# untitled.net
KiCad netlist of a schematic drawn in EAGLE
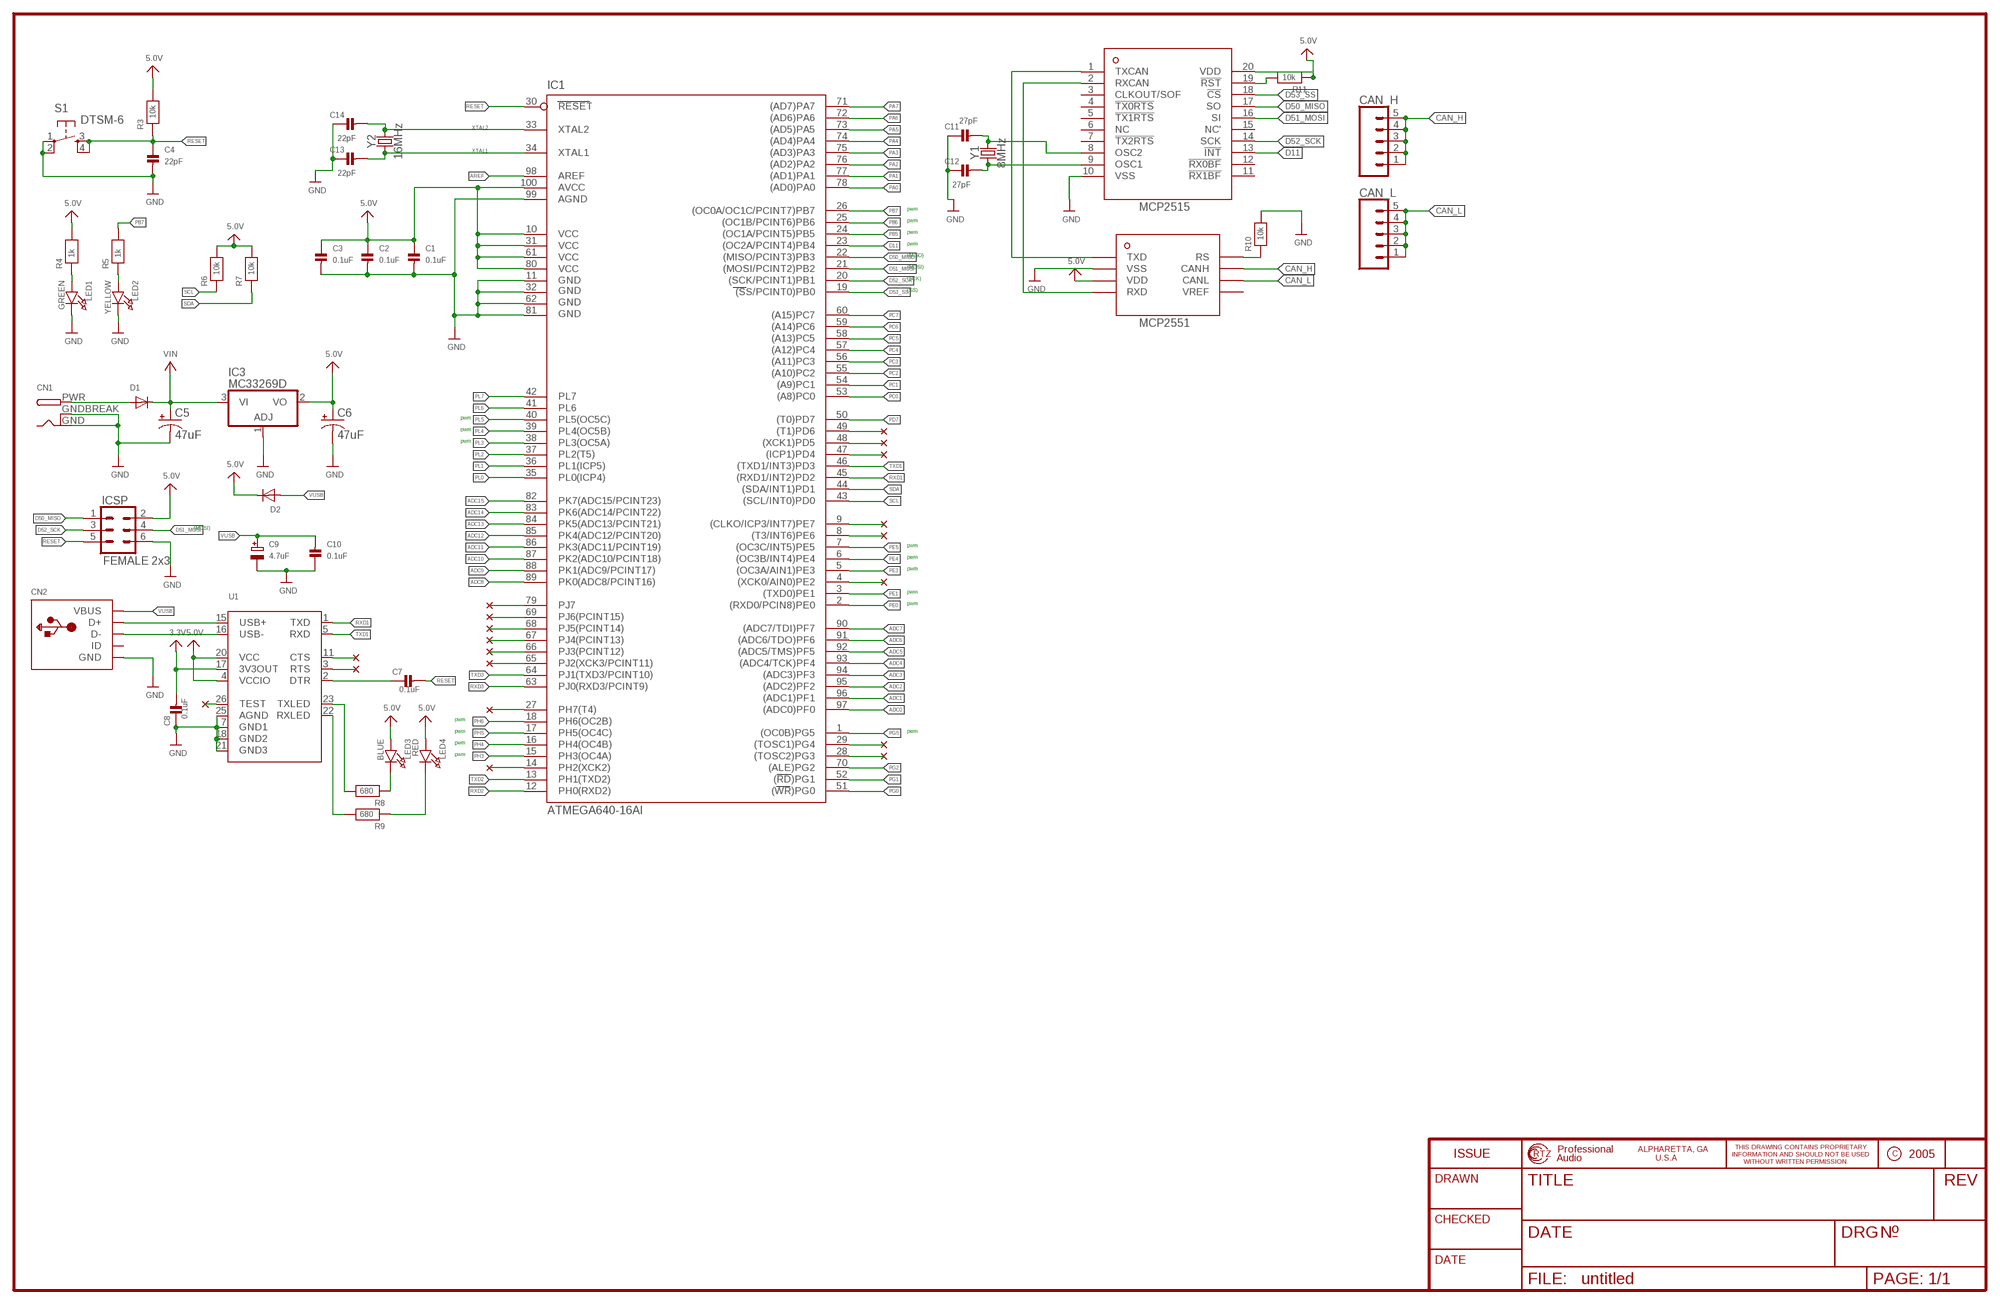
[diagram p0: schematic, sheet 1]

(export (version "E")
  (design (tool "Eeschema 10.0.6"))
  (components
    (comp (ref "C1")
      (value "0.1uF")
      (footprint "eagle-import:0805")
      (libsource (lib "eagle-import") (part "CAP_CERAMIC0805"))
    )
    (comp (ref "C2")
      (value "0.1uF")
      (footprint "eagle-import:0805")
      (libsource (lib "eagle-import") (part "CAP_CERAMIC0805"))
    )
    (comp (ref "C3")
      (value "0.1uF")
      (footprint "eagle-import:0805")
      (libsource (lib "eagle-import") (part "CAP_CERAMIC0805"))
    )
    (comp (ref "C4")
      (value "22pF")
      (footprint "eagle-import:0805")
      (libsource (lib "eagle-import") (part "CAP_CERAMIC0805"))
    )
    (comp (ref "C5")
      (value "47uF")
      (footprint "eagle-import:PANASONIC_D")
      (libsource (lib "eagle-import") (part "CPOL-USD"))
    )
    (comp (ref "C6")
      (value "47uF")
      (footprint "eagle-import:PANASONIC_D")
      (libsource (lib "eagle-import") (part "CPOL-USD"))
    )
    (comp (ref "C7")
      (value "0.1uF")
      (footprint "eagle-import:0805")
      (libsource (lib "eagle-import") (part "CAP_CERAMIC0805"))
    )
    (comp (ref "C8")
      (value "0.1uF")
      (footprint "eagle-import:0805")
      (libsource (lib "eagle-import") (part "CAP_CERAMIC0805"))
    )
    (comp (ref "C9")
      (value "4.7uF")
      (footprint "eagle-import:EIA7343-31_D-W")
      (libsource (lib "eagle-import") (part "CAP_TANTALUMD/7343_WAVE"))
    )
    (comp (ref "C10")
      (value "0.1uF")
      (footprint "eagle-import:0805")
      (libsource (lib "eagle-import") (part "CAP_CERAMIC0805"))
    )
    (comp (ref "C11")
      (value "27pF")
      (footprint "eagle-import:0805")
      (libsource (lib "eagle-import") (part "CAP_CERAMIC0805"))
    )
    (comp (ref "C12")
      (value "27pF")
      (footprint "eagle-import:0805")
      (libsource (lib "eagle-import") (part "CAP_CERAMIC0805"))
    )
    (comp (ref "C13")
      (value "22pF")
      (footprint "eagle-import:0805")
      (libsource (lib "eagle-import") (part "CAP_CERAMIC0805"))
    )
    (comp (ref "C14")
      (value "22pF")
      (footprint "eagle-import:0805")
      (libsource (lib "eagle-import") (part "CAP_CERAMIC0805"))
    )
    (comp (ref "CAN_H")
      (value "CONN_05SCREW")
      (footprint "eagle-import:SCREWTERMINAL-3.5MM-5")
      (libsource (lib "eagle-import") (part "CONN_05SCREW"))
    )
    (comp (ref "CAN_L")
      (value "CONN_05SCREW")
      (footprint "eagle-import:SCREWTERMINAL-3.5MM-5")
      (libsource (lib "eagle-import") (part "CONN_05SCREW"))
    )
    (comp (ref "CN1")
      (value "DCBARRELPTH")
      (footprint "eagle-import:DCJACK_2MM_PTH")
      (libsource (lib "eagle-import") (part "DCBARRELPTH"))
    )
    (comp (ref "CN2")
      (value "USBMINIB")
      (footprint "eagle-import:USB-MINIB")
      (libsource (lib "eagle-import") (part "USBMINIB"))
    )
    (comp (ref "D1")
      (value "DIODESOD-123")
      (footprint "eagle-import:SOD-123")
      (libsource (lib "eagle-import") (part "DIODESOD-123"))
    )
    (comp (ref "D2")
      (value "DIODESOD-123")
      (footprint "eagle-import:SOD-123")
      (libsource (lib "eagle-import") (part "DIODESOD-123"))
    )
    (comp (ref "IC1")
      (value "ATMEGA640-16AI")
      (footprint "eagle-import:TQFP100")
      (libsource (lib "eagle-import") (part "ATMEGAAI640-16"))
    )
    (comp (ref "IC3")
      (value "MC33269D")
      (footprint "eagle-import:DPACK")
      (libsource (lib "eagle-import") (part "MC33269?D"))
    )
    (comp (ref "ICSP")
      (value "FEMALE 2x3")
      (footprint "eagle-import:2X3")
      (libsource (lib "eagle-import") (part "CONN_03X2FEMALE"))
    )
    (comp (ref "LED1")
      (value "GREEN")
      (footprint "eagle-import:CHIPLED_0805")
      (libsource (lib "eagle-import") (part "LED0805"))
    )
    (comp (ref "LED2")
      (value "YELLOW")
      (footprint "eagle-import:CHIPLED_0805")
      (libsource (lib "eagle-import") (part "LED0805"))
    )
    (comp (ref "LED3")
      (value "BLUE")
      (footprint "eagle-import:CHIPLED_0805")
      (libsource (lib "eagle-import") (part "LED0805"))
    )
    (comp (ref "LED4")
      (value "RED")
      (footprint "eagle-import:CHIPLED_0805")
      (libsource (lib "eagle-import") (part "LED0805"))
    )
    (comp (ref "R3")
      (value "10k")
      (footprint "eagle-import:0805")
      (libsource (lib "eagle-import") (part "RESISTOR0805"))
    )
    (comp (ref "R4")
      (value "1k")
      (footprint "eagle-import:0805")
      (libsource (lib "eagle-import") (part "RESISTOR0805"))
    )
    (comp (ref "R5")
      (value "1k")
      (footprint "eagle-import:0805")
      (libsource (lib "eagle-import") (part "RESISTOR0805"))
    )
    (comp (ref "R6")
      (value "10k")
      (footprint "eagle-import:0805")
      (libsource (lib "eagle-import") (part "RESISTOR0805"))
    )
    (comp (ref "R7")
      (value "10k")
      (footprint "eagle-import:0805")
      (libsource (lib "eagle-import") (part "RESISTOR0805"))
    )
    (comp (ref "R8")
      (value "680")
      (footprint "eagle-import:0805")
      (libsource (lib "eagle-import") (part "RESISTOR0805"))
    )
    (comp (ref "R9")
      (value "680")
      (footprint "eagle-import:0805")
      (libsource (lib "eagle-import") (part "RESISTOR0805"))
    )
    (comp (ref "R10")
      (value "10k")
      (footprint "eagle-import:0805")
      (libsource (lib "eagle-import") (part "RESISTOR0805"))
    )
    (comp (ref "R11")
      (value "10k")
      (footprint "eagle-import:0805")
      (libsource (lib "eagle-import") (part "RESISTOR0805"))
    )
    (comp (ref "S1")
      (value "DTSM-6")
      (footprint "eagle-import:DTSM-6")
      (libsource (lib "eagle-import") (part "DTSM-6"))
    )
    (comp (ref "U$6") (value "NC") (footprint "eagle-import:NC") (libsource (lib "eagle-import") (part "NC")))
    (comp (ref "U$7") (value "NC") (footprint "eagle-import:NC") (libsource (lib "eagle-import") (part "NC")))
    (comp (ref "U$8") (value "NC") (footprint "eagle-import:NC") (libsource (lib "eagle-import") (part "NC")))
    (comp (ref "U$9") (value "NC") (footprint "eagle-import:NC") (libsource (lib "eagle-import") (part "NC")))
    (comp (ref "U$10")
      (value "NC")
      (footprint "eagle-import:NC")
      (libsource (lib "eagle-import") (part "NC"))
    )
    (comp (ref "U$11")
      (value "NC")
      (footprint "eagle-import:NC")
      (libsource (lib "eagle-import") (part "NC"))
    )
    (comp (ref "U$12")
      (value "NC")
      (footprint "eagle-import:NC")
      (libsource (lib "eagle-import") (part "NC"))
    )
    (comp (ref "U$13")
      (value "NC")
      (footprint "eagle-import:NC")
      (libsource (lib "eagle-import") (part "NC"))
    )
    (comp (ref "U$14")
      (value "NC")
      (footprint "eagle-import:NC")
      (libsource (lib "eagle-import") (part "NC"))
    )
    (comp (ref "U$15")
      (value "NC")
      (footprint "eagle-import:NC")
      (libsource (lib "eagle-import") (part "NC"))
    )
    (comp (ref "U$16")
      (value "NC")
      (footprint "eagle-import:NC")
      (libsource (lib "eagle-import") (part "NC"))
    )
    (comp (ref "U$17")
      (value "NC")
      (footprint "eagle-import:NC")
      (libsource (lib "eagle-import") (part "NC"))
    )
    (comp (ref "U$18")
      (value "NC")
      (footprint "eagle-import:NC")
      (libsource (lib "eagle-import") (part "NC"))
    )
    (comp (ref "U$19")
      (value "NC")
      (footprint "eagle-import:NC")
      (libsource (lib "eagle-import") (part "NC"))
    )
    (comp (ref "U$20")
      (value "NC")
      (footprint "eagle-import:NC")
      (libsource (lib "eagle-import") (part "NC"))
    )
    (comp (ref "U$21")
      (value "NC")
      (footprint "eagle-import:NC")
      (libsource (lib "eagle-import") (part "NC"))
    )
    (comp (ref "U$37")
      (value "NC")
      (footprint "eagle-import:NC")
      (libsource (lib "eagle-import") (part "NC"))
    )
    (comp (ref "U$38")
      (value "NC")
      (footprint "eagle-import:NC")
      (libsource (lib "eagle-import") (part "NC"))
    )
    (comp (ref "U$42")
      (value "NC")
      (footprint "eagle-import:NC")
      (libsource (lib "eagle-import") (part "NC"))
    )
    (comp (ref "U$45")
      (value "MCP2515")
      (footprint "eagle-import:TSSOP20")
      (libsource (lib "eagle-import") (part "MCP2515"))
    )
    (comp (ref "U$46")
      (value "MCP2551")
      (footprint "eagle-import:SOIC-8")
      (libsource (lib "eagle-import") (part "MCP2551"))
    )
    (comp (ref "U1")
      (value "FT232RLSSOP28")
      (footprint "eagle-import:SSOP28DB")
      (libsource (lib "eagle-import") (part "FT232RLSSOP28"))
    )
    (comp (ref "Y1")
      (value "8MHz")
      (footprint "eagle-import:HC49US")
      (libsource (lib "eagle-import") (part "CRYSTALPTH-HC49US"))
    )
    (comp (ref "Y2")
      (value "16MHz")
      (footprint "eagle-import:HC49US")
      (libsource (lib "eagle-import") (part "CRYSTALPTH-HC49US"))
    )
  )
  (nets
    (net (code "1") (name "/XTAL1") (class "Default")
      (node (ref "C13") (pin "2") (pinfunction "P$2_2") (pintype "passive"))
      (node (ref "IC1") (pin "34") (pinfunction "XTAL1_34") (pintype "input"))
      (node (ref "Y2") (pin "1") (pinfunction "1_1") (pintype "passive"))
    )
    (net (code "2") (name "/XTAL2") (class "Default")
      (node (ref "C14") (pin "2") (pinfunction "P$2_2") (pintype "passive"))
      (node (ref "IC1") (pin "33") (pinfunction "XTAL2_33") (pintype "output"))
      (node (ref "Y2") (pin "2") (pinfunction "2_2") (pintype "passive"))
    )
    (net (code "3") (name "3.3V") (class "Default")
      (node (ref "C8") (pin "2") (pinfunction "P$2_2") (pintype "passive"))
      (node (ref "U1") (pin "17") (pinfunction "3V3OUT_17") (pintype "power_in"))
    )
    (net (code "4") (name "5.0V") (class "Default")
      (node (ref "C1") (pin "1") (pinfunction "P$1_1") (pintype "passive"))
      (node (ref "C2") (pin "1") (pinfunction "P$1_1") (pintype "passive"))
      (node (ref "C3") (pin "1") (pinfunction "P$1_1") (pintype "passive"))
      (node (ref "C6") (pin "+") (pinfunction "+_+") (pintype "passive"))
      (node (ref "D2") (pin "C") (pinfunction "C_C") (pintype "passive"))
      (node (ref "IC1") (pin "10") (pinfunction "VCC_10") (pintype "power_in"))
      (node (ref "IC1") (pin "100") (pinfunction "AVCC_100") (pintype "power_in"))
      (node (ref "IC1") (pin "31") (pinfunction "VCC1_31") (pintype "power_in"))
      (node (ref "IC1") (pin "61") (pinfunction "VCC2_61") (pintype "power_in"))
      (node (ref "IC1") (pin "80") (pinfunction "VCC3_80") (pintype "power_in"))
      (node (ref "IC3") (pin "2") (pinfunction "VO_2") (pintype "passive"))
      (node (ref "ICSP") (pin "2") (pinfunction "2_2") (pintype "bidirectional"))
      (node (ref "LED3") (pin "A") (pinfunction "A_A") (pintype "passive"))
      (node (ref "LED4") (pin "A") (pinfunction "A_A") (pintype "passive"))
      (node (ref "R11") (pin "1") (pinfunction "1_1") (pintype "passive"))
      (node (ref "R3") (pin "2") (pinfunction "2_2") (pintype "passive"))
      (node (ref "R4") (pin "2") (pinfunction "2_2") (pintype "passive"))
      (node (ref "R6") (pin "2") (pinfunction "2_2") (pintype "passive"))
      (node (ref "R7") (pin "2") (pinfunction "2_2") (pintype "passive"))
      (node (ref "U$45") (pin "20") (pinfunction "VDD_20") (pintype "bidirectional"))
      (node (ref "U$46") (pin "VDD") (pinfunction "VDD_VDD") (pintype "bidirectional"))
      (node (ref "U1") (pin "20") (pinfunction "VCC_20") (pintype "power_in"))
      (node (ref "U1") (pin "4") (pinfunction "VCCIO_4") (pintype "power_in"))
    )
    (net (code "5") (name "ADC0") (class "Default")
      (node (ref "IC1") (pin "97") (pinfunction "(ADC0)PF0_97") (pintype "bidirectional"))
    )
    (net (code "6") (name "ADC1") (class "Default")
      (node (ref "IC1") (pin "96") (pinfunction "(ADC1)PF1_96") (pintype "bidirectional"))
    )
    (net (code "7") (name "ADC2") (class "Default")
      (node (ref "IC1") (pin "95") (pinfunction "(ADC2)PF2_95") (pintype "bidirectional"))
    )
    (net (code "8") (name "ADC3") (class "Default")
      (node (ref "IC1") (pin "94") (pinfunction "(ADC3)PF3_94") (pintype "bidirectional"))
    )
    (net (code "9") (name "ADC4") (class "Default")
      (node (ref "IC1") (pin "93") (pinfunction "(ADC4/TCK)PF4_93") (pintype "bidirectional"))
    )
    (net (code "10") (name "ADC5") (class "Default")
      (node (ref "IC1") (pin "92") (pinfunction "(ADC5/TMS)PF5_92") (pintype "bidirectional"))
    )
    (net (code "11") (name "ADC6") (class "Default")
      (node (ref "IC1") (pin "91") (pinfunction "(ADC6/TDO)PF6_91") (pintype "bidirectional"))
    )
    (net (code "12") (name "ADC7") (class "Default")
      (node (ref "IC1") (pin "90") (pinfunction "(ADC7/TDI)PF7_90") (pintype "bidirectional"))
    )
    (net (code "13") (name "ADC8") (class "Default")
      (node (ref "IC1") (pin "89") (pinfunction "PK0(ADC8/PCINT16)_89") (pintype "bidirectional"))
    )
    (net (code "14") (name "ADC9") (class "Default")
      (node (ref "IC1") (pin "88") (pinfunction "PK1(ADC9/PCINT17)_88") (pintype "bidirectional"))
    )
    (net (code "15") (name "ADC10") (class "Default")
      (node (ref "IC1") (pin "87") (pinfunction "PK2(ADC10/PCINT18)_87") (pintype "bidirectional"))
    )
    (net (code "16") (name "ADC11") (class "Default")
      (node (ref "IC1") (pin "86") (pinfunction "PK3(ADC11/PCINT19)_86") (pintype "bidirectional"))
    )
    (net (code "17") (name "ADC12") (class "Default")
      (node (ref "IC1") (pin "85") (pinfunction "PK4(ADC12/PCINT20)_85") (pintype "bidirectional"))
    )
    (net (code "18") (name "ADC13") (class "Default")
      (node (ref "IC1") (pin "84") (pinfunction "PK5(ADC13/PCINT21)_84") (pintype "bidirectional"))
    )
    (net (code "19") (name "ADC14") (class "Default")
      (node (ref "IC1") (pin "83") (pinfunction "PK6(ADC14/PCINT22)_83") (pintype "bidirectional"))
    )
    (net (code "20") (name "ADC15") (class "Default")
      (node (ref "IC1") (pin "82") (pinfunction "PK7(ADC15/PCINT23)_82") (pintype "bidirectional"))
    )
    (net (code "21") (name "AREF") (class "Default")
      (node (ref "IC1") (pin "98") (pinfunction "AREF_98") (pintype "bidirectional"))
    )
    (net (code "22") (name "CAN_H") (class "Default")
      (node (ref "CAN_H") (pin "1") (pinfunction "1_1") (pintype "passive"))
      (node (ref "CAN_H") (pin "2") (pinfunction "2_2") (pintype "passive"))
      (node (ref "CAN_H") (pin "3") (pinfunction "3_3") (pintype "passive"))
      (node (ref "CAN_H") (pin "4") (pinfunction "4_4") (pintype "passive"))
      (node (ref "CAN_H") (pin "5") (pinfunction "5_5") (pintype "passive"))
      (node (ref "U$46") (pin "CANH") (pinfunction "CANH_CANH") (pintype "bidirectional"))
    )
    (net (code "23") (name "CAN_L") (class "Default")
      (node (ref "CAN_L") (pin "1") (pinfunction "1_1") (pintype "passive"))
      (node (ref "CAN_L") (pin "2") (pinfunction "2_2") (pintype "passive"))
      (node (ref "CAN_L") (pin "3") (pinfunction "3_3") (pintype "passive"))
      (node (ref "CAN_L") (pin "4") (pinfunction "4_4") (pintype "passive"))
      (node (ref "CAN_L") (pin "5") (pinfunction "5_5") (pintype "passive"))
      (node (ref "U$46") (pin "CANL") (pinfunction "CANL_CANL") (pintype "bidirectional"))
    )
    (net (code "24") (name "D11") (class "Default")
      (node (ref "IC1") (pin "23") (pinfunction "(OC2A/PCINT4)PB4_23") (pintype "bidirectional"))
      (node (ref "U$45") (pin "13") (pinfunction "~{INT}_13") (pintype "bidirectional"))
    )
    (net (code "25") (name "D50_MISO") (class "Default")
      (node (ref "IC1") (pin "22") (pinfunction "(MISO/PCINT3)PB3_22") (pintype "bidirectional"))
      (node (ref "ICSP") (pin "1") (pinfunction "1_1") (pintype "bidirectional"))
      (node (ref "U$45") (pin "17") (pinfunction "SO_17") (pintype "bidirectional"))
    )
    (net (code "26") (name "D51_MOSI") (class "Default")
      (node (ref "IC1") (pin "21") (pinfunction "(MOSI/PCINT2)PB2_21") (pintype "bidirectional"))
      (node (ref "ICSP") (pin "4") (pinfunction "4_4") (pintype "bidirectional"))
      (node (ref "U$45") (pin "16") (pinfunction "SI_16") (pintype "bidirectional"))
    )
    (net (code "27") (name "D52_SCK") (class "Default")
      (node (ref "IC1") (pin "20") (pinfunction "(SCK/PCINT1)PB1_20") (pintype "bidirectional"))
      (node (ref "ICSP") (pin "3") (pinfunction "3_3") (pintype "bidirectional"))
      (node (ref "U$45") (pin "14") (pinfunction "SCK_14") (pintype "bidirectional"))
    )
    (net (code "28") (name "D53_SS") (class "Default")
      (node (ref "IC1") (pin "19") (pinfunction "(SS/PCINT0)PB0_19") (pintype "bidirectional"))
      (node (ref "U$45") (pin "18") (pinfunction "~{CS}_18") (pintype "bidirectional"))
    )
    (net (code "29") (name "GND") (class "Default")
      (node (ref "C1") (pin "2") (pinfunction "P$2_2") (pintype "passive"))
      (node (ref "C10") (pin "1") (pinfunction "P$1_1") (pintype "passive"))
      (node (ref "C11") (pin "1") (pinfunction "P$1_1") (pintype "passive"))
      (node (ref "C12") (pin "1") (pinfunction "P$1_1") (pintype "passive"))
      (node (ref "C13") (pin "1") (pinfunction "P$1_1") (pintype "passive"))
      (node (ref "C14") (pin "1") (pinfunction "P$1_1") (pintype "passive"))
      (node (ref "C2") (pin "2") (pinfunction "P$2_2") (pintype "passive"))
      (node (ref "C3") (pin "2") (pinfunction "P$2_2") (pintype "passive"))
      (node (ref "C4") (pin "2") (pinfunction "P$2_2") (pintype "passive"))
      (node (ref "C5") (pin "-") (pinfunction "-_-") (pintype "passive"))
      (node (ref "C6") (pin "-") (pinfunction "-_-") (pintype "passive"))
      (node (ref "C8") (pin "1") (pinfunction "P$1_1") (pintype "passive"))
      (node (ref "C9") (pin "-") (pinfunction "-_-") (pintype "passive"))
      (node (ref "CN1") (pin "GND") (pinfunction "GND_GND") (pintype "power_in"))
      (node (ref "CN1") (pin "GNDBREAK") (pinfunction "GNDBREAK_GNDBREAK") (pintype "power_in"))
      (node (ref "CN2") (pin "GND") (pinfunction "GND_GND") (pintype "power_in"))
      (node (ref "IC1") (pin "11") (pinfunction "GND_11") (pintype "power_in"))
      (node (ref "IC1") (pin "32") (pinfunction "GND1_32") (pintype "power_in"))
      (node (ref "IC1") (pin "62") (pinfunction "GND2_62") (pintype "power_in"))
      (node (ref "IC1") (pin "81") (pinfunction "GND3_81") (pintype "power_in"))
      (node (ref "IC1") (pin "99") (pinfunction "AGND_99") (pintype "power_in"))
      (node (ref "IC3") (pin "1") (pinfunction "ADJ_1") (pintype "input"))
      (node (ref "ICSP") (pin "6") (pinfunction "6_6") (pintype "bidirectional"))
      (node (ref "LED1") (pin "C") (pinfunction "C_C") (pintype "passive"))
      (node (ref "LED2") (pin "C") (pinfunction "C_C") (pintype "passive"))
      (node (ref "R10") (pin "2") (pinfunction "2_2") (pintype "passive"))
      (node (ref "S1") (pin "1") (pinfunction "1_1") (pintype "passive"))
      (node (ref "S1") (pin "2") (pinfunction "2_2") (pintype "passive"))
      (node (ref "U$45") (pin "10") (pinfunction "VSS_10") (pintype "bidirectional"))
      (node (ref "U$46") (pin "VSS") (pinfunction "VSS_VSS") (pintype "bidirectional"))
      (node (ref "U1") (pin "18") (pinfunction "GND2_18") (pintype "power_in"))
      (node (ref "U1") (pin "21") (pinfunction "GND3_21") (pintype "power_in"))
      (node (ref "U1") (pin "25") (pinfunction "AGND_25") (pintype "power_in"))
      (node (ref "U1") (pin "7") (pinfunction "GND1_7") (pintype "power_in"))
    )
    (net (code "30") (name "Net-(C7-P$1)") (class "Default")
      (node (ref "C7") (pin "1") (pinfunction "P$1_1") (pintype "passive"))
      (node (ref "U1") (pin "2") (pinfunction "DTR_2") (pintype "bidirectional"))
    )
    (net (code "31") (name "Net-(C11-P$2)") (class "Default")
      (node (ref "C11") (pin "2") (pinfunction "P$2_2") (pintype "passive"))
      (node (ref "U$45") (pin "8") (pinfunction "OSC2_8") (pintype "bidirectional"))
      (node (ref "Y1") (pin "2") (pinfunction "2_2") (pintype "passive"))
    )
    (net (code "32") (name "Net-(C12-P$2)") (class "Default")
      (node (ref "C12") (pin "2") (pinfunction "P$2_2") (pintype "passive"))
      (node (ref "U$45") (pin "9") (pinfunction "OSC1_9") (pintype "bidirectional"))
      (node (ref "Y1") (pin "1") (pinfunction "1_1") (pintype "passive"))
    )
    (net (code "33") (name "Net-(CN1-PadPWR)") (class "Default")
      (node (ref "CN1") (pin "PWR") (pinfunction "PWR_PWR") (pintype "power_in"))
      (node (ref "D1") (pin "A") (pinfunction "A_A") (pintype "passive"))
    )
    (net (code "34") (name "Net-(LED1-PadA)") (class "Default")
      (node (ref "LED1") (pin "A") (pinfunction "A_A") (pintype "passive"))
      (node (ref "R4") (pin "1") (pinfunction "1_1") (pintype "passive"))
    )
    (net (code "35") (name "Net-(LED2-PadA)") (class "Default")
      (node (ref "LED2") (pin "A") (pinfunction "A_A") (pintype "passive"))
      (node (ref "R5") (pin "1") (pinfunction "1_1") (pintype "passive"))
    )
    (net (code "36") (name "Net-(LED3-PadC)") (class "Default")
      (node (ref "LED3") (pin "C") (pinfunction "C_C") (pintype "passive"))
      (node (ref "R8") (pin "1") (pinfunction "1_1") (pintype "passive"))
    )
    (net (code "37") (name "Net-(LED4-PadC)") (class "Default")
      (node (ref "LED4") (pin "C") (pinfunction "C_C") (pintype "passive"))
      (node (ref "R9") (pin "1") (pinfunction "1_1") (pintype "passive"))
    )
    (net (code "38") (name "Net-(R10-Pad1)") (class "Default")
      (node (ref "R10") (pin "1") (pinfunction "1_1") (pintype "passive"))
      (node (ref "U$46") (pin "RS") (pinfunction "RS_RS") (pintype "bidirectional"))
    )
    (net (code "39") (name "Net-(U$45-RXCAN)") (class "Default")
      (node (ref "U$45") (pin "2") (pinfunction "RXCAN_2") (pintype "bidirectional"))
      (node (ref "U$46") (pin "RXD") (pinfunction "RXD_RXD") (pintype "bidirectional"))
    )
    (net (code "40") (name "Net-(U$45-TXCAN)") (class "Default")
      (node (ref "U$45") (pin "1") (pinfunction "TXCAN_1") (pintype "bidirectional"))
      (node (ref "U$46") (pin "TXD") (pinfunction "TXD_TXD") (pintype "bidirectional"))
    )
    (net (code "41") (name "Net-(U$45-~{RST})") (class "Default")
      (node (ref "R11") (pin "2") (pinfunction "2_2") (pintype "passive"))
      (node (ref "U$45") (pin "19") (pinfunction "~{RST}_19") (pintype "bidirectional"))
    )
    (net (code "42") (name "Net-(U1-RXLED)") (class "Default")
      (node (ref "R9") (pin "2") (pinfunction "2_2") (pintype "passive"))
      (node (ref "U1") (pin "22") (pinfunction "RXLED_22") (pintype "bidirectional"))
    )
    (net (code "43") (name "Net-(U1-TXLED)") (class "Default")
      (node (ref "R8") (pin "2") (pinfunction "2_2") (pintype "passive"))
      (node (ref "U1") (pin "23") (pinfunction "TXLED_23") (pintype "bidirectional"))
    )
    (net (code "44") (name "Net-(U1-USB+)") (class "Default")
      (node (ref "CN2") (pin "D+") (pinfunction "D+_D+") (pintype "bidirectional"))
      (node (ref "U1") (pin "15") (pinfunction "USB+_15") (pintype "bidirectional"))
    )
    (net (code "45") (name "Net-(U1-USB-)") (class "Default")
      (node (ref "CN2") (pin "D-") (pinfunction "D-_D-") (pintype "bidirectional"))
      (node (ref "U1") (pin "16") (pinfunction "USB-_16") (pintype "bidirectional"))
    )
    (net (code "46") (name "PA0") (class "Default")
      (node (ref "IC1") (pin "78") (pinfunction "(AD0)PA0_78") (pintype "bidirectional"))
    )
    (net (code "47") (name "PA1") (class "Default")
      (node (ref "IC1") (pin "77") (pinfunction "(AD1)PA1_77") (pintype "bidirectional"))
    )
    (net (code "48") (name "PA2") (class "Default")
      (node (ref "IC1") (pin "76") (pinfunction "(AD2)PA2_76") (pintype "bidirectional"))
    )
    (net (code "49") (name "PA3") (class "Default")
      (node (ref "IC1") (pin "75") (pinfunction "(AD3)PA3_75") (pintype "bidirectional"))
    )
    (net (code "50") (name "PA4") (class "Default")
      (node (ref "IC1") (pin "74") (pinfunction "(AD4)PA4_74") (pintype "bidirectional"))
    )
    (net (code "51") (name "PA5") (class "Default")
      (node (ref "IC1") (pin "73") (pinfunction "(AD5)PA5_73") (pintype "bidirectional"))
    )
    (net (code "52") (name "PA6") (class "Default")
      (node (ref "IC1") (pin "72") (pinfunction "(AD6)PA6_72") (pintype "bidirectional"))
    )
    (net (code "53") (name "PA7") (class "Default")
      (node (ref "IC1") (pin "71") (pinfunction "(AD7)PA7_71") (pintype "bidirectional"))
    )
    (net (code "54") (name "PB5") (class "Default")
      (node (ref "IC1") (pin "24") (pinfunction "(OC1A/PCINT5)PB5_24") (pintype "bidirectional"))
    )
    (net (code "55") (name "PB6") (class "Default")
      (node (ref "IC1") (pin "25") (pinfunction "(OC1B/PCINT6)PB6_25") (pintype "bidirectional"))
    )
    (net (code "56") (name "PB7") (class "Default")
      (node (ref "IC1") (pin "26") (pinfunction "(OC0A/OC1C/PCINT7)PB7_26") (pintype "bidirectional"))
      (node (ref "R5") (pin "2") (pinfunction "2_2") (pintype "passive"))
    )
    (net (code "57") (name "PC0") (class "Default")
      (node (ref "IC1") (pin "53") (pinfunction "(A8)PC0_53") (pintype "bidirectional"))
    )
    (net (code "58") (name "PC1") (class "Default")
      (node (ref "IC1") (pin "54") (pinfunction "(A9)PC1_54") (pintype "bidirectional"))
    )
    (net (code "59") (name "PC2") (class "Default")
      (node (ref "IC1") (pin "55") (pinfunction "(A10)PC2_55") (pintype "bidirectional"))
    )
    (net (code "60") (name "PC3") (class "Default")
      (node (ref "IC1") (pin "56") (pinfunction "(A11)PC3_56") (pintype "bidirectional"))
    )
    (net (code "61") (name "PC4") (class "Default")
      (node (ref "IC1") (pin "57") (pinfunction "(A12)PC4_57") (pintype "bidirectional"))
    )
    (net (code "62") (name "PC5") (class "Default")
      (node (ref "IC1") (pin "58") (pinfunction "(A13)PC5_58") (pintype "bidirectional"))
    )
    (net (code "63") (name "PC6") (class "Default")
      (node (ref "IC1") (pin "59") (pinfunction "(A14)PC6_59") (pintype "bidirectional"))
    )
    (net (code "64") (name "PC7") (class "Default")
      (node (ref "IC1") (pin "60") (pinfunction "(A15)PC7_60") (pintype "bidirectional"))
    )
    (net (code "65") (name "PD7") (class "Default")
      (node (ref "IC1") (pin "50") (pinfunction "(T0)PD7_50") (pintype "bidirectional"))
    )
    (net (code "66") (name "PE0") (class "Default")
      (node (ref "IC1") (pin "2") (pinfunction "(RXD0/PCIN8)PE0_2") (pintype "bidirectional"))
    )
    (net (code "67") (name "PE1") (class "Default")
      (node (ref "IC1") (pin "3") (pinfunction "(TXD0)PE1_3") (pintype "bidirectional"))
    )
    (net (code "68") (name "PE3") (class "Default")
      (node (ref "IC1") (pin "5") (pinfunction "(OC3A/AIN1)PE3_5") (pintype "bidirectional"))
    )
    (net (code "69") (name "PE4") (class "Default")
      (node (ref "IC1") (pin "6") (pinfunction "(OC3B/INT4)PE4_6") (pintype "bidirectional"))
    )
    (net (code "70") (name "PE5") (class "Default")
      (node (ref "IC1") (pin "7") (pinfunction "(OC3C/INT5)PE5_7") (pintype "bidirectional"))
    )
    (net (code "71") (name "PG0") (class "Default")
      (node (ref "IC1") (pin "51") (pinfunction "(WR)PG0_51") (pintype "bidirectional"))
    )
    (net (code "72") (name "PG1") (class "Default")
      (node (ref "IC1") (pin "52") (pinfunction "(RD)PG1_52") (pintype "bidirectional"))
    )
    (net (code "73") (name "PG2") (class "Default")
      (node (ref "IC1") (pin "70") (pinfunction "(ALE)PG2_70") (pintype "bidirectional"))
    )
    (net (code "74") (name "PG5") (class "Default")
      (node (ref "IC1") (pin "1") (pinfunction "(OC0B)PG5_1") (pintype "bidirectional"))
    )
    (net (code "75") (name "PH3") (class "Default")
      (node (ref "IC1") (pin "15") (pinfunction "PH3(OC4A)_15") (pintype "bidirectional"))
    )
    (net (code "76") (name "PH4") (class "Default")
      (node (ref "IC1") (pin "16") (pinfunction "PH4(OC4B)_16") (pintype "bidirectional"))
    )
    (net (code "77") (name "PH5") (class "Default")
      (node (ref "IC1") (pin "17") (pinfunction "PH5(OC4C)_17") (pintype "bidirectional"))
    )
    (net (code "78") (name "PH6") (class "Default")
      (node (ref "IC1") (pin "18") (pinfunction "PH6(OC2B)_18") (pintype "bidirectional"))
    )
    (net (code "79") (name "PL0") (class "Default")
      (node (ref "IC1") (pin "35") (pinfunction "PL0(ICP4)_35") (pintype "bidirectional"))
    )
    (net (code "80") (name "PL1") (class "Default")
      (node (ref "IC1") (pin "36") (pinfunction "PL1(ICP5)_36") (pintype "bidirectional"))
    )
    (net (code "81") (name "PL2") (class "Default")
      (node (ref "IC1") (pin "37") (pinfunction "PL2(T5)_37") (pintype "bidirectional"))
    )
    (net (code "82") (name "PL3") (class "Default")
      (node (ref "IC1") (pin "38") (pinfunction "PL3(OC5A)_38") (pintype "bidirectional"))
    )
    (net (code "83") (name "PL4") (class "Default")
      (node (ref "IC1") (pin "39") (pinfunction "PL4(OC5B)_39") (pintype "bidirectional"))
    )
    (net (code "84") (name "PL5") (class "Default")
      (node (ref "IC1") (pin "40") (pinfunction "PL5(OC5C)_40") (pintype "bidirectional"))
    )
    (net (code "85") (name "PL6") (class "Default")
      (node (ref "IC1") (pin "41") (pinfunction "PL6_41") (pintype "bidirectional"))
    )
    (net (code "86") (name "PL7") (class "Default")
      (node (ref "IC1") (pin "42") (pinfunction "PL7_42") (pintype "bidirectional"))
    )
    (net (code "87") (name "RESET") (class "Default")
      (node (ref "C4") (pin "1") (pinfunction "P$1_1") (pintype "passive"))
      (node (ref "C7") (pin "2") (pinfunction "P$2_2") (pintype "passive"))
      (node (ref "IC1") (pin "30") (pinfunction "RESET_30") (pintype "input"))
      (node (ref "ICSP") (pin "5") (pinfunction "5_5") (pintype "bidirectional"))
      (node (ref "R3") (pin "1") (pinfunction "1_1") (pintype "passive"))
      (node (ref "S1") (pin "3") (pinfunction "3_3") (pintype "passive"))
      (node (ref "S1") (pin "4") (pinfunction "4_4") (pintype "passive"))
    )
    (net (code "88") (name "RXD1") (class "Default")
      (node (ref "IC1") (pin "45") (pinfunction "(RXD1/INT2)PD2_45") (pintype "bidirectional"))
      (node (ref "U1") (pin "1") (pinfunction "TXD_1") (pintype "output"))
    )
    (net (code "89") (name "RXD2") (class "Default")
      (node (ref "IC1") (pin "12") (pinfunction "PH0(RXD2)_12") (pintype "bidirectional"))
    )
    (net (code "90") (name "RXD3") (class "Default")
      (node (ref "IC1") (pin "63") (pinfunction "PJ0(RXD3/PCINT9)_63") (pintype "bidirectional"))
    )
    (net (code "91") (name "SCL") (class "Default")
      (node (ref "IC1") (pin "43") (pinfunction "(SCL/INT0)PD0_43") (pintype "bidirectional"))
      (node (ref "R6") (pin "1") (pinfunction "1_1") (pintype "passive"))
    )
    (net (code "92") (name "SDA") (class "Default")
      (node (ref "IC1") (pin "44") (pinfunction "(SDA/INT1)PD1_44") (pintype "bidirectional"))
      (node (ref "R7") (pin "1") (pinfunction "1_1") (pintype "passive"))
    )
    (net (code "93") (name "TXD1") (class "Default")
      (node (ref "IC1") (pin "46") (pinfunction "(TXD1/INT3)PD3_46") (pintype "bidirectional"))
      (node (ref "U1") (pin "5") (pinfunction "RXD_5") (pintype "input"))
    )
    (net (code "94") (name "TXD2") (class "Default")
      (node (ref "IC1") (pin "13") (pinfunction "PH1(TXD2)_13") (pintype "bidirectional"))
    )
    (net (code "95") (name "TXD3") (class "Default")
      (node (ref "IC1") (pin "64") (pinfunction "PJ1(TXD3/PCINT10)_64") (pintype "bidirectional"))
    )
    (net (code "96") (name "VIN") (class "Default")
      (node (ref "C5") (pin "+") (pinfunction "+_+") (pintype "passive"))
      (node (ref "D1") (pin "C") (pinfunction "C_C") (pintype "passive"))
      (node (ref "IC3") (pin "3") (pinfunction "VI_3") (pintype "input"))
    )
    (net (code "97") (name "VUSB") (class "Default")
      (node (ref "C10") (pin "2") (pinfunction "P$2_2") (pintype "passive"))
      (node (ref "C9") (pin "+") (pinfunction "+_+") (pintype "passive"))
      (node (ref "CN2") (pin "VBUS") (pinfunction "VBUS_VBUS") (pintype "power_in"))
      (node (ref "D2") (pin "A") (pinfunction "A_A") (pintype "passive"))
    )
    (net (code "98") (name "unconnected-(CN2-PadID)") (class "Default")
      (node (ref "CN2") (pin "ID") (pinfunction "ID_ID") (pintype "bidirectional"))
    )
    (net (code "99") (name "unconnected-(IC1-(CLKO{slash}ICP3{slash}INT7)PE7-Pad9)") (class "Default")
      (node (ref "IC1") (pin "9") (pinfunction "(CLKO/ICP3/INT7)PE7_9") (pintype "bidirectional"))
    )
    (net (code "100") (name "unconnected-(IC1-(ICP1)PD4-Pad47)") (class "Default")
      (node (ref "IC1") (pin "47") (pinfunction "(ICP1)PD4_47") (pintype "bidirectional"))
    )
    (net (code "101") (name "unconnected-(IC1-(T1)PD6-Pad49)") (class "Default")
      (node (ref "IC1") (pin "49") (pinfunction "(T1)PD6_49") (pintype "bidirectional"))
    )
    (net (code "102") (name "unconnected-(IC1-(T3{slash}INT6)PE6-Pad8)") (class "Default")
      (node (ref "IC1") (pin "8") (pinfunction "(T3/INT6)PE6_8") (pintype "bidirectional"))
    )
    (net (code "103") (name "unconnected-(IC1-(TOSC1)PG4-Pad29)") (class "Default")
      (node (ref "IC1") (pin "29") (pinfunction "(TOSC1)PG4_29") (pintype "bidirectional"))
    )
    (net (code "104") (name "unconnected-(IC1-(TOSC2)PG3-Pad28)") (class "Default")
      (node (ref "IC1") (pin "28") (pinfunction "(TOSC2)PG3_28") (pintype "bidirectional"))
    )
    (net (code "105") (name "unconnected-(IC1-(XCK0{slash}AIN0)PE2-Pad4)") (class "Default")
      (node (ref "IC1") (pin "4") (pinfunction "(XCK0/AIN0)PE2_4") (pintype "bidirectional"))
    )
    (net (code "106") (name "unconnected-(IC1-(XCK1)PD5-Pad48)") (class "Default")
      (node (ref "IC1") (pin "48") (pinfunction "(XCK1)PD5_48") (pintype "bidirectional"))
    )
    (net (code "107") (name "unconnected-(IC1-PH2(XCK2)-Pad14)") (class "Default")
      (node (ref "IC1") (pin "14") (pinfunction "PH2(XCK2)_14") (pintype "bidirectional"))
    )
    (net (code "108") (name "unconnected-(IC1-PH7(T4)-Pad27)") (class "Default")
      (node (ref "IC1") (pin "27") (pinfunction "PH7(T4)_27") (pintype "bidirectional"))
    )
    (net (code "109") (name "unconnected-(IC1-PJ2(XCK3{slash}PCINT11)-Pad65)") (class "Default")
      (node (ref "IC1") (pin "65") (pinfunction "PJ2(XCK3/PCINT11)_65") (pintype "bidirectional"))
    )
    (net (code "110") (name "unconnected-(IC1-PJ3(PCINT12)-Pad66)") (class "Default")
      (node (ref "IC1") (pin "66") (pinfunction "PJ3(PCINT12)_66") (pintype "bidirectional"))
    )
    (net (code "111") (name "unconnected-(IC1-PJ4(PCINT13)-Pad67)") (class "Default")
      (node (ref "IC1") (pin "67") (pinfunction "PJ4(PCINT13)_67") (pintype "bidirectional"))
    )
    (net (code "112") (name "unconnected-(IC1-PJ5(PCINT14)-Pad68)") (class "Default")
      (node (ref "IC1") (pin "68") (pinfunction "PJ5(PCINT14)_68") (pintype "bidirectional"))
    )
    (net (code "113") (name "unconnected-(IC1-PJ6(PCINT15)-Pad69)") (class "Default")
      (node (ref "IC1") (pin "69") (pinfunction "PJ6(PCINT15)_69") (pintype "bidirectional"))
    )
    (net (code "114") (name "unconnected-(IC1-PJ7-Pad79)") (class "Default")
      (node (ref "IC1") (pin "79") (pinfunction "PJ7_79") (pintype "bidirectional"))
    )
    (net (code "115") (name "unconnected-(U$45-CLKOUT{slash}SOF-Pad3)") (class "Default")
      (node (ref "U$45") (pin "3") (pinfunction "CLKOUT/SOF_3") (pintype "bidirectional"))
    )
    (net (code "116") (name "unconnected-(U$45-NC'-Pad15)") (class "Default")
      (node (ref "U$45") (pin "15") (pinfunction "NC'_15") (pintype "bidirectional"))
    )
    (net (code "117") (name "unconnected-(U$45-NC-Pad6)") (class "Default")
      (node (ref "U$45") (pin "6") (pinfunction "NC_6") (pintype "bidirectional"))
    )
    (net (code "118") (name "unconnected-(U$45-~{RX0BF}-Pad12)") (class "Default")
      (node (ref "U$45") (pin "12") (pinfunction "~{RX0BF}_12") (pintype "bidirectional"))
    )
    (net (code "119") (name "unconnected-(U$45-~{RX1BF}-Pad11)") (class "Default")
      (node (ref "U$45") (pin "11") (pinfunction "~{RX1BF}_11") (pintype "bidirectional"))
    )
    (net (code "120") (name "unconnected-(U$45-~{TX0RTS}-Pad4)") (class "Default")
      (node (ref "U$45") (pin "4") (pinfunction "~{TX0RTS}_4") (pintype "bidirectional"))
    )
    (net (code "121") (name "unconnected-(U$45-~{TX1RTS}-Pad5)") (class "Default")
      (node (ref "U$45") (pin "5") (pinfunction "~{TX1RTS}_5") (pintype "bidirectional"))
    )
    (net (code "122") (name "unconnected-(U$45-~{TX2RTS}-Pad7)") (class "Default")
      (node (ref "U$45") (pin "7") (pinfunction "~{TX2RTS}_7") (pintype "bidirectional"))
    )
    (net (code "123") (name "unconnected-(U$46-PadVREF)") (class "Default")
      (node (ref "U$46") (pin "VREF") (pinfunction "VREF_VREF") (pintype "bidirectional"))
    )
    (net (code "124") (name "unconnected-(U1-CTS-Pad11)") (class "Default")
      (node (ref "U1") (pin "11") (pinfunction "CTS_11") (pintype "bidirectional"))
    )
    (net (code "125") (name "unconnected-(U1-RTS-Pad3)") (class "Default")
      (node (ref "U1") (pin "3") (pinfunction "RTS_3") (pintype "bidirectional"))
    )
    (net (code "126") (name "unconnected-(U1-TEST-Pad26)") (class "Default")
      (node (ref "U1") (pin "26") (pinfunction "TEST_26") (pintype "input"))
    )
  )
)
